# PCB-BI8-1x6SC3.net
KiCad netlist of a schematic drawn in EAGLE
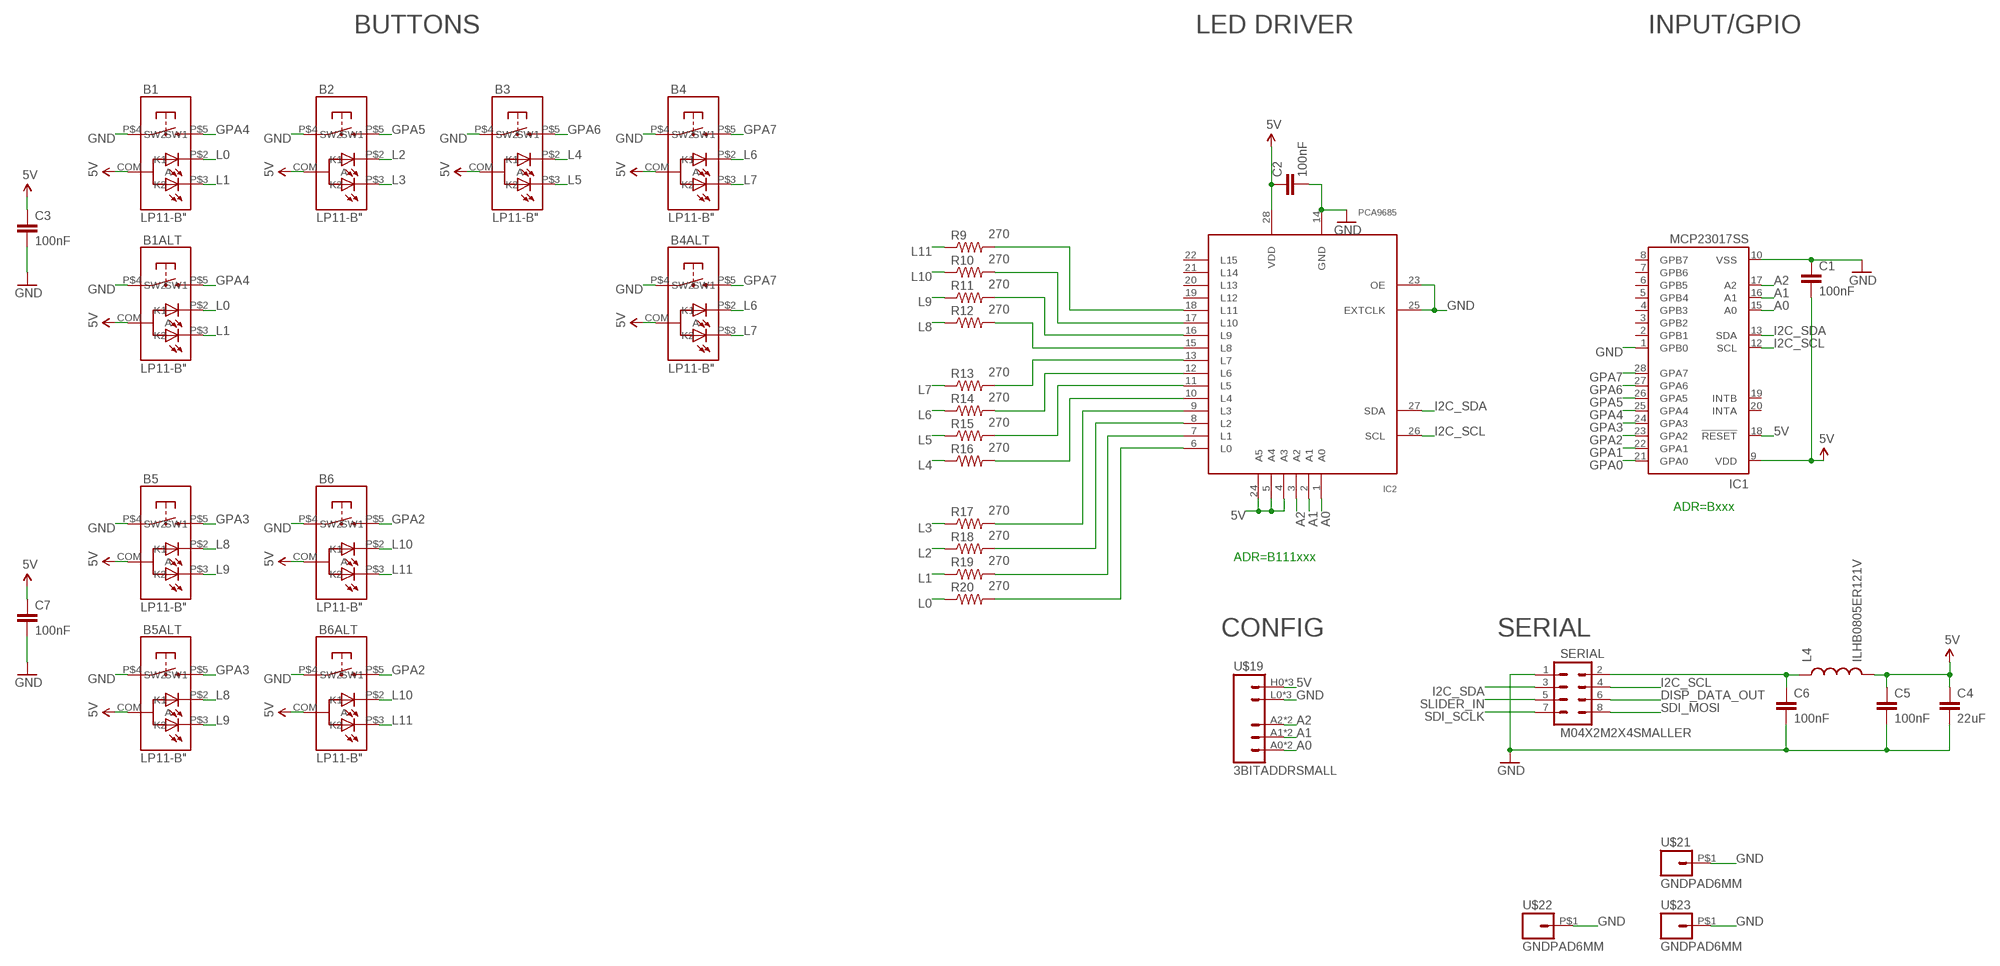
[diagram p0: schematic, sheet 1]

(export (version "E")
  (design (tool "Eeschema 10.0.6"))
  (components
    (comp (ref "B1")
      (value "LP11-B\"")
      (footprint "eagle-import:LP11")
      (libsource (lib "eagle-import") (part "LP11-B{dblquote}"))
    )
    (comp (ref "B1ALT")
      (value "LP11-B\"")
      (footprint "eagle-import:LP11")
      (libsource (lib "eagle-import") (part "LP11-B{dblquote}"))
    )
    (comp (ref "B2")
      (value "LP11-B\"")
      (footprint "eagle-import:LP11")
      (libsource (lib "eagle-import") (part "LP11-B{dblquote}"))
    )
    (comp (ref "B3")
      (value "LP11-B\"")
      (footprint "eagle-import:LP11")
      (libsource (lib "eagle-import") (part "LP11-B{dblquote}"))
    )
    (comp (ref "B4")
      (value "LP11-B\"")
      (footprint "eagle-import:LP11")
      (libsource (lib "eagle-import") (part "LP11-B{dblquote}"))
    )
    (comp (ref "B4ALT")
      (value "LP11-B\"")
      (footprint "eagle-import:LP11")
      (libsource (lib "eagle-import") (part "LP11-B{dblquote}"))
    )
    (comp (ref "B5")
      (value "LP11-B\"")
      (footprint "eagle-import:LP11")
      (libsource (lib "eagle-import") (part "LP11-B{dblquote}"))
    )
    (comp (ref "B5ALT")
      (value "LP11-B\"")
      (footprint "eagle-import:LP11")
      (libsource (lib "eagle-import") (part "LP11-B{dblquote}"))
    )
    (comp (ref "B6")
      (value "LP11-B\"")
      (footprint "eagle-import:LP11")
      (libsource (lib "eagle-import") (part "LP11-B{dblquote}"))
    )
    (comp (ref "B6ALT")
      (value "LP11-B\"")
      (footprint "eagle-import:LP11")
      (libsource (lib "eagle-import") (part "LP11-B{dblquote}"))
    )
    (comp (ref "C1")
      (value "100nF")
      (footprint "eagle-import:0603-CAP")
      (libsource (lib "eagle-import") (part "CAP0603-CAP"))
    )
    (comp (ref "C2")
      (value "100nF")
      (footprint "eagle-import:0603-CAP")
      (libsource (lib "eagle-import") (part "CAP0603-CAP"))
    )
    (comp (ref "C3")
      (value "100nF")
      (footprint "eagle-import:0603-CAP")
      (libsource (lib "eagle-import") (part "CAP0603-CAP"))
    )
    (comp (ref "C4")
      (value "22uF")
      (footprint "eagle-import:0805")
      (libsource (lib "eagle-import") (part "CAP0805"))
    )
    (comp (ref "C5")
      (value "100nF")
      (footprint "eagle-import:0603-CAP")
      (libsource (lib "eagle-import") (part "CAP0603-CAP"))
    )
    (comp (ref "C6")
      (value "100nF")
      (footprint "eagle-import:0603-CAP")
      (libsource (lib "eagle-import") (part "CAP0603-CAP"))
    )
    (comp (ref "C7")
      (value "100nF")
      (footprint "eagle-import:0603-CAP")
      (libsource (lib "eagle-import") (part "CAP0603-CAP"))
    )
    (comp (ref "IC1")
      (value "MCP23017SS")
      (footprint "eagle-import:SSOP28")
      (fields
        (field (name "MF") "MICROCHIP")
        (field (name "MPN") "MCP23017-E/SS")
        (field (name "MPN_1") "MCP23017-E/SS")
        (field (name "OC_FARNELL") "1467674")
        (field (name "OC_NEWARK") "31K2960")
      )
      (libsource (lib "eagle-import") (part "MCP23017SS"))
    )
    (comp (ref "IC2")
      (value "PCA9685")
      (footprint "eagle-import:TSSOP28")
      (libsource (lib "eagle-import") (part "PCA9685"))
    )
    (comp (ref "L4")
      (value "ILHB0805ER121V")
      (footprint "eagle-import:0805")
      (libsource (lib "eagle-import") (part "INDUCTOR0805"))
    )
    (comp (ref "R9")
      (value "270")
      (footprint "eagle-import:0603-RES")
      (libsource (lib "eagle-import") (part "RESISTOR0603-RES"))
    )
    (comp (ref "R10")
      (value "270")
      (footprint "eagle-import:0603-RES")
      (libsource (lib "eagle-import") (part "RESISTOR0603-RES"))
    )
    (comp (ref "R11")
      (value "270")
      (footprint "eagle-import:0603-RES")
      (libsource (lib "eagle-import") (part "RESISTOR0603-RES"))
    )
    (comp (ref "R12")
      (value "270")
      (footprint "eagle-import:0603-RES")
      (libsource (lib "eagle-import") (part "RESISTOR0603-RES"))
    )
    (comp (ref "R13")
      (value "270")
      (footprint "eagle-import:0603-RES")
      (libsource (lib "eagle-import") (part "RESISTOR0603-RES"))
    )
    (comp (ref "R14")
      (value "270")
      (footprint "eagle-import:0603-RES")
      (libsource (lib "eagle-import") (part "RESISTOR0603-RES"))
    )
    (comp (ref "R15")
      (value "270")
      (footprint "eagle-import:0603-RES")
      (libsource (lib "eagle-import") (part "RESISTOR0603-RES"))
    )
    (comp (ref "R16")
      (value "270")
      (footprint "eagle-import:0603-RES")
      (libsource (lib "eagle-import") (part "RESISTOR0603-RES"))
    )
    (comp (ref "R17")
      (value "270")
      (footprint "eagle-import:0603-RES")
      (libsource (lib "eagle-import") (part "RESISTOR0603-RES"))
    )
    (comp (ref "R18")
      (value "270")
      (footprint "eagle-import:0603-RES")
      (libsource (lib "eagle-import") (part "RESISTOR0603-RES"))
    )
    (comp (ref "R19")
      (value "270")
      (footprint "eagle-import:0603-RES")
      (libsource (lib "eagle-import") (part "RESISTOR0603-RES"))
    )
    (comp (ref "R20")
      (value "270")
      (footprint "eagle-import:0603-RES")
      (libsource (lib "eagle-import") (part "RESISTOR0603-RES"))
    )
    (comp (ref "SERIAL")
      (value "M04X2M2X4SMALLER")
      (footprint "eagle-import:M2X4SMALLER")
      (libsource (lib "eagle-import") (part "M04X2M2X4SMALLER"))
    )
    (comp (ref "U$19")
      (value "3BITADDRSMALL")
      (footprint "eagle-import:3BITADDR_SMALL")
      (libsource (lib "eagle-import") (part "3BITADDRSMALL"))
    )
    (comp (ref "U$21")
      (value "GNDPAD6MM")
      (footprint "eagle-import:3.2MMPAD6MM")
      (libsource (lib "eagle-import") (part "GNDPAD6MM"))
    )
    (comp (ref "U$22")
      (value "GNDPAD6MM")
      (footprint "eagle-import:3.2MMPAD6MM")
      (libsource (lib "eagle-import") (part "GNDPAD6MM"))
    )
    (comp (ref "U$23")
      (value "GNDPAD6MM")
      (footprint "eagle-import:3.2MMPAD6MM")
      (libsource (lib "eagle-import") (part "GNDPAD6MM"))
    )
  )
  (nets
    (net (code "1") (name "/A0") (class "Default")
      (node (ref "IC1") (pin "15") (pinfunction "A0_15") (pintype "input"))
      (node (ref "IC2") (pin "1") (pinfunction "A0_1") (pintype "input"))
      (node (ref "U$19") (pin "A0") (pinfunction "A0_A0") (pintype "passive"))
      (node (ref "U$19") (pin "AS0") (pinfunction "A0_AS0") (pintype "passive"))
    )
    (net (code "2") (name "/A1") (class "Default")
      (node (ref "IC1") (pin "16") (pinfunction "A1_16") (pintype "input"))
      (node (ref "IC2") (pin "2") (pinfunction "A1_2") (pintype "input"))
      (node (ref "U$19") (pin "A1") (pinfunction "A1_A1") (pintype "passive"))
      (node (ref "U$19") (pin "AS1") (pinfunction "A1_AS1") (pintype "passive"))
    )
    (net (code "3") (name "/A2") (class "Default")
      (node (ref "IC1") (pin "17") (pinfunction "A2_17") (pintype "input"))
      (node (ref "IC2") (pin "3") (pinfunction "A2_3") (pintype "input"))
      (node (ref "U$19") (pin "A2") (pinfunction "A2_A2") (pintype "passive"))
      (node (ref "U$19") (pin "AS2") (pinfunction "A2_AS2") (pintype "passive"))
    )
    (net (code "4") (name "/DISP_DATA_OUT") (class "Default")
      (node (ref "SERIAL") (pin "6") (pinfunction "6_6") (pintype "passive"))
    )
    (net (code "5") (name "/GPA0") (class "Default")
      (node (ref "IC1") (pin "21") (pinfunction "GPA0_21") (pintype "bidirectional"))
    )
    (net (code "6") (name "/GPA1") (class "Default")
      (node (ref "IC1") (pin "22") (pinfunction "GPA1_22") (pintype "bidirectional"))
    )
    (net (code "7") (name "/GPA2") (class "Default")
      (node (ref "B6") (pin "P$5") (pinfunction "SW2_P$5") (pintype "bidirectional"))
      (node (ref "B6ALT") (pin "P$5") (pinfunction "SW2_P$5") (pintype "bidirectional"))
      (node (ref "IC1") (pin "23") (pinfunction "GPA2_23") (pintype "bidirectional"))
    )
    (net (code "8") (name "/GPA3") (class "Default")
      (node (ref "B5") (pin "P$5") (pinfunction "SW2_P$5") (pintype "bidirectional"))
      (node (ref "B5ALT") (pin "P$5") (pinfunction "SW2_P$5") (pintype "bidirectional"))
      (node (ref "IC1") (pin "24") (pinfunction "GPA3_24") (pintype "bidirectional"))
    )
    (net (code "9") (name "/GPA4") (class "Default")
      (node (ref "B1") (pin "P$5") (pinfunction "SW2_P$5") (pintype "bidirectional"))
      (node (ref "B1ALT") (pin "P$5") (pinfunction "SW2_P$5") (pintype "bidirectional"))
      (node (ref "IC1") (pin "25") (pinfunction "GPA4_25") (pintype "bidirectional"))
    )
    (net (code "10") (name "/GPA5") (class "Default")
      (node (ref "B2") (pin "P$5") (pinfunction "SW2_P$5") (pintype "bidirectional"))
      (node (ref "IC1") (pin "26") (pinfunction "GPA5_26") (pintype "bidirectional"))
    )
    (net (code "11") (name "/GPA6") (class "Default")
      (node (ref "B3") (pin "P$5") (pinfunction "SW2_P$5") (pintype "bidirectional"))
      (node (ref "IC1") (pin "27") (pinfunction "GPA6_27") (pintype "bidirectional"))
    )
    (net (code "12") (name "/GPA7") (class "Default")
      (node (ref "B4") (pin "P$5") (pinfunction "SW2_P$5") (pintype "bidirectional"))
      (node (ref "B4ALT") (pin "P$5") (pinfunction "SW2_P$5") (pintype "bidirectional"))
      (node (ref "IC1") (pin "28") (pinfunction "GPA7_28") (pintype "bidirectional"))
    )
    (net (code "13") (name "/I2C_SCL") (class "Default")
      (node (ref "IC1") (pin "12") (pinfunction "SCL_12") (pintype "input"))
      (node (ref "IC2") (pin "26") (pinfunction "SCL_26") (pintype "input"))
      (node (ref "SERIAL") (pin "4") (pinfunction "4_4") (pintype "passive"))
    )
    (net (code "14") (name "/I2C_SDA") (class "Default")
      (node (ref "IC1") (pin "13") (pinfunction "SDA_13") (pintype "bidirectional"))
      (node (ref "IC2") (pin "27") (pinfunction "SDA_27") (pintype "input"))
      (node (ref "SERIAL") (pin "3") (pinfunction "3_3") (pintype "passive"))
    )
    (net (code "15") (name "/L0") (class "Default")
      (node (ref "B1") (pin "P$2") (pinfunction "K1_P$2") (pintype "bidirectional"))
      (node (ref "B1ALT") (pin "P$2") (pinfunction "K1_P$2") (pintype "bidirectional"))
      (node (ref "R20") (pin "1") (pinfunction "1_1") (pintype "passive"))
    )
    (net (code "16") (name "/L1") (class "Default")
      (node (ref "B1") (pin "P$3") (pinfunction "K2_P$3") (pintype "bidirectional"))
      (node (ref "B1ALT") (pin "P$3") (pinfunction "K2_P$3") (pintype "bidirectional"))
      (node (ref "R19") (pin "1") (pinfunction "1_1") (pintype "passive"))
    )
    (net (code "17") (name "/L2") (class "Default")
      (node (ref "B2") (pin "P$2") (pinfunction "K1_P$2") (pintype "bidirectional"))
      (node (ref "R18") (pin "1") (pinfunction "1_1") (pintype "passive"))
    )
    (net (code "18") (name "/L3") (class "Default")
      (node (ref "B2") (pin "P$3") (pinfunction "K2_P$3") (pintype "bidirectional"))
      (node (ref "R17") (pin "1") (pinfunction "1_1") (pintype "passive"))
    )
    (net (code "19") (name "/L4") (class "Default")
      (node (ref "B3") (pin "P$2") (pinfunction "K1_P$2") (pintype "bidirectional"))
      (node (ref "R16") (pin "1") (pinfunction "1_1") (pintype "passive"))
    )
    (net (code "20") (name "/L5") (class "Default")
      (node (ref "B3") (pin "P$3") (pinfunction "K2_P$3") (pintype "bidirectional"))
      (node (ref "R15") (pin "1") (pinfunction "1_1") (pintype "passive"))
    )
    (net (code "21") (name "/L6") (class "Default")
      (node (ref "B4") (pin "P$2") (pinfunction "K1_P$2") (pintype "bidirectional"))
      (node (ref "B4ALT") (pin "P$2") (pinfunction "K1_P$2") (pintype "bidirectional"))
      (node (ref "R14") (pin "1") (pinfunction "1_1") (pintype "passive"))
    )
    (net (code "22") (name "/L7") (class "Default")
      (node (ref "B4") (pin "P$3") (pinfunction "K2_P$3") (pintype "bidirectional"))
      (node (ref "B4ALT") (pin "P$3") (pinfunction "K2_P$3") (pintype "bidirectional"))
      (node (ref "R13") (pin "1") (pinfunction "1_1") (pintype "passive"))
    )
    (net (code "23") (name "/L8") (class "Default")
      (node (ref "B5") (pin "P$2") (pinfunction "K1_P$2") (pintype "bidirectional"))
      (node (ref "B5ALT") (pin "P$2") (pinfunction "K1_P$2") (pintype "bidirectional"))
      (node (ref "R12") (pin "1") (pinfunction "1_1") (pintype "passive"))
    )
    (net (code "24") (name "/L9") (class "Default")
      (node (ref "B5") (pin "P$3") (pinfunction "K2_P$3") (pintype "bidirectional"))
      (node (ref "B5ALT") (pin "P$3") (pinfunction "K2_P$3") (pintype "bidirectional"))
      (node (ref "R11") (pin "1") (pinfunction "1_1") (pintype "passive"))
    )
    (net (code "25") (name "/L10") (class "Default")
      (node (ref "B6") (pin "P$2") (pinfunction "K1_P$2") (pintype "bidirectional"))
      (node (ref "B6ALT") (pin "P$2") (pinfunction "K1_P$2") (pintype "bidirectional"))
      (node (ref "R10") (pin "1") (pinfunction "1_1") (pintype "passive"))
    )
    (net (code "26") (name "/L11") (class "Default")
      (node (ref "B6") (pin "P$3") (pinfunction "K2_P$3") (pintype "bidirectional"))
      (node (ref "B6ALT") (pin "P$3") (pinfunction "K2_P$3") (pintype "bidirectional"))
      (node (ref "R9") (pin "1") (pinfunction "1_1") (pintype "passive"))
    )
    (net (code "27") (name "/SDI_MOSI") (class "Default")
      (node (ref "SERIAL") (pin "8") (pinfunction "8_8") (pintype "passive"))
    )
    (net (code "28") (name "/SDI_SCLK") (class "Default")
      (node (ref "SERIAL") (pin "7") (pinfunction "7_7") (pintype "passive"))
    )
    (net (code "29") (name "/SLIDER_IN") (class "Default")
      (node (ref "SERIAL") (pin "5") (pinfunction "5_5") (pintype "passive"))
    )
    (net (code "30") (name "5V") (class "Default")
      (node (ref "B1") (pin "COM") (pinfunction "A_COM") (pintype "bidirectional"))
      (node (ref "B1ALT") (pin "COM") (pinfunction "A_COM") (pintype "bidirectional"))
      (node (ref "B2") (pin "COM") (pinfunction "A_COM") (pintype "bidirectional"))
      (node (ref "B3") (pin "COM") (pinfunction "A_COM") (pintype "bidirectional"))
      (node (ref "B4") (pin "COM") (pinfunction "A_COM") (pintype "bidirectional"))
      (node (ref "B4ALT") (pin "COM") (pinfunction "A_COM") (pintype "bidirectional"))
      (node (ref "B5") (pin "COM") (pinfunction "A_COM") (pintype "bidirectional"))
      (node (ref "B5ALT") (pin "COM") (pinfunction "A_COM") (pintype "bidirectional"))
      (node (ref "B6") (pin "COM") (pinfunction "A_COM") (pintype "bidirectional"))
      (node (ref "B6ALT") (pin "COM") (pinfunction "A_COM") (pintype "bidirectional"))
      (node (ref "C1") (pin "2") (pinfunction "2_2") (pintype "passive"))
      (node (ref "C2") (pin "1") (pinfunction "1_1") (pintype "passive"))
      (node (ref "C3") (pin "1") (pinfunction "1_1") (pintype "passive"))
      (node (ref "C4") (pin "1") (pinfunction "1_1") (pintype "passive"))
      (node (ref "C5") (pin "1") (pinfunction "1_1") (pintype "passive"))
      (node (ref "C7") (pin "1") (pinfunction "1_1") (pintype "passive"))
      (node (ref "IC1") (pin "18") (pinfunction "~{RESET}_18") (pintype "input"))
      (node (ref "IC1") (pin "9") (pinfunction "VDD_9") (pintype "power_in"))
      (node (ref "IC2") (pin "24") (pinfunction "A5_24") (pintype "input"))
      (node (ref "IC2") (pin "28") (pinfunction "VDD_28") (pintype "power_in"))
      (node (ref "IC2") (pin "4") (pinfunction "A3_4") (pintype "input"))
      (node (ref "IC2") (pin "5") (pinfunction "A4_5") (pintype "input"))
      (node (ref "L4") (pin "2") (pinfunction "2_2") (pintype "passive"))
      (node (ref "U$19") (pin "H0") (pinfunction "VCC_H0") (pintype "passive"))
      (node (ref "U$19") (pin "H1") (pinfunction "VCC_H1") (pintype "passive"))
      (node (ref "U$19") (pin "H2") (pinfunction "VCC_H2") (pintype "passive"))
    )
    (net (code "31") (name "GND") (class "Default")
      (node (ref "B1") (pin "P$4") (pinfunction "SW1_P$4") (pintype "bidirectional"))
      (node (ref "B1ALT") (pin "P$4") (pinfunction "SW1_P$4") (pintype "bidirectional"))
      (node (ref "B2") (pin "P$4") (pinfunction "SW1_P$4") (pintype "bidirectional"))
      (node (ref "B3") (pin "P$4") (pinfunction "SW1_P$4") (pintype "bidirectional"))
      (node (ref "B4") (pin "P$4") (pinfunction "SW1_P$4") (pintype "bidirectional"))
      (node (ref "B4ALT") (pin "P$4") (pinfunction "SW1_P$4") (pintype "bidirectional"))
      (node (ref "B5") (pin "P$4") (pinfunction "SW1_P$4") (pintype "bidirectional"))
      (node (ref "B5ALT") (pin "P$4") (pinfunction "SW1_P$4") (pintype "bidirectional"))
      (node (ref "B6") (pin "P$4") (pinfunction "SW1_P$4") (pintype "bidirectional"))
      (node (ref "B6ALT") (pin "P$4") (pinfunction "SW1_P$4") (pintype "bidirectional"))
      (node (ref "C1") (pin "1") (pinfunction "1_1") (pintype "passive"))
      (node (ref "C2") (pin "2") (pinfunction "2_2") (pintype "passive"))
      (node (ref "C3") (pin "2") (pinfunction "2_2") (pintype "passive"))
      (node (ref "C4") (pin "2") (pinfunction "2_2") (pintype "passive"))
      (node (ref "C5") (pin "2") (pinfunction "2_2") (pintype "passive"))
      (node (ref "C6") (pin "2") (pinfunction "2_2") (pintype "passive"))
      (node (ref "C7") (pin "2") (pinfunction "2_2") (pintype "passive"))
      (node (ref "IC1") (pin "1") (pinfunction "GPB0_1") (pintype "bidirectional"))
      (node (ref "IC1") (pin "10") (pinfunction "VSS_10") (pintype "power_in"))
      (node (ref "IC2") (pin "14") (pinfunction "GND_14") (pintype "power_in"))
      (node (ref "IC2") (pin "23") (pinfunction "OE_23") (pintype "input"))
      (node (ref "IC2") (pin "25") (pinfunction "EXTCLK_25") (pintype "input"))
      (node (ref "SERIAL") (pin "1") (pinfunction "1_1") (pintype "passive"))
      (node (ref "U$19") (pin "L0") (pinfunction "GND_L0") (pintype "passive"))
      (node (ref "U$19") (pin "L1") (pinfunction "GND_L1") (pintype "passive"))
      (node (ref "U$19") (pin "L2") (pinfunction "GND_L2") (pintype "passive"))
      (node (ref "U$21") (pin "P$1") (pinfunction "1_P$1") (pintype "passive"))
      (node (ref "U$22") (pin "P$1") (pinfunction "1_P$1") (pintype "passive"))
      (node (ref "U$23") (pin "P$1") (pinfunction "1_P$1") (pintype "passive"))
    )
    (net (code "32") (name "Net-(C6-Pad1)") (class "Default")
      (node (ref "C6") (pin "1") (pinfunction "1_1") (pintype "passive"))
      (node (ref "L4") (pin "1") (pinfunction "1_1") (pintype "passive"))
      (node (ref "SERIAL") (pin "2") (pinfunction "2_2") (pintype "passive"))
    )
    (net (code "33") (name "Net-(IC2-L0)") (class "Default")
      (node (ref "IC2") (pin "6") (pinfunction "L0_6") (pintype "output"))
      (node (ref "R20") (pin "2") (pinfunction "2_2") (pintype "passive"))
    )
    (net (code "34") (name "Net-(IC2-L1)") (class "Default")
      (node (ref "IC2") (pin "7") (pinfunction "L1_7") (pintype "output"))
      (node (ref "R19") (pin "2") (pinfunction "2_2") (pintype "passive"))
    )
    (net (code "35") (name "Net-(IC2-L2)") (class "Default")
      (node (ref "IC2") (pin "8") (pinfunction "L2_8") (pintype "output"))
      (node (ref "R18") (pin "2") (pinfunction "2_2") (pintype "passive"))
    )
    (net (code "36") (name "Net-(IC2-L3)") (class "Default")
      (node (ref "IC2") (pin "9") (pinfunction "L3_9") (pintype "output"))
      (node (ref "R17") (pin "2") (pinfunction "2_2") (pintype "passive"))
    )
    (net (code "37") (name "Net-(IC2-L4)") (class "Default")
      (node (ref "IC2") (pin "10") (pinfunction "L4_10") (pintype "output"))
      (node (ref "R16") (pin "2") (pinfunction "2_2") (pintype "passive"))
    )
    (net (code "38") (name "Net-(IC2-L5)") (class "Default")
      (node (ref "IC2") (pin "11") (pinfunction "L5_11") (pintype "output"))
      (node (ref "R15") (pin "2") (pinfunction "2_2") (pintype "passive"))
    )
    (net (code "39") (name "Net-(IC2-L6)") (class "Default")
      (node (ref "IC2") (pin "12") (pinfunction "L6_12") (pintype "output"))
      (node (ref "R14") (pin "2") (pinfunction "2_2") (pintype "passive"))
    )
    (net (code "40") (name "Net-(IC2-L7)") (class "Default")
      (node (ref "IC2") (pin "13") (pinfunction "L7_13") (pintype "output"))
      (node (ref "R13") (pin "2") (pinfunction "2_2") (pintype "passive"))
    )
    (net (code "41") (name "Net-(IC2-L8)") (class "Default")
      (node (ref "IC2") (pin "15") (pinfunction "L8_15") (pintype "output"))
      (node (ref "R12") (pin "2") (pinfunction "2_2") (pintype "passive"))
    )
    (net (code "42") (name "Net-(IC2-L9)") (class "Default")
      (node (ref "IC2") (pin "16") (pinfunction "L9_16") (pintype "output"))
      (node (ref "R11") (pin "2") (pinfunction "2_2") (pintype "passive"))
    )
    (net (code "43") (name "Net-(IC2-L10)") (class "Default")
      (node (ref "IC2") (pin "17") (pinfunction "L10_17") (pintype "output"))
      (node (ref "R10") (pin "2") (pinfunction "2_2") (pintype "passive"))
    )
    (net (code "44") (name "Net-(IC2-L11)") (class "Default")
      (node (ref "IC2") (pin "18") (pinfunction "L11_18") (pintype "output"))
      (node (ref "R9") (pin "2") (pinfunction "2_2") (pintype "passive"))
    )
    (net (code "45") (name "unconnected-(IC1-GPB1-Pad2)") (class "Default")
      (node (ref "IC1") (pin "2") (pinfunction "GPB1_2") (pintype "bidirectional"))
    )
    (net (code "46") (name "unconnected-(IC1-GPB2-Pad3)") (class "Default")
      (node (ref "IC1") (pin "3") (pinfunction "GPB2_3") (pintype "bidirectional"))
    )
    (net (code "47") (name "unconnected-(IC1-GPB3-Pad4)") (class "Default")
      (node (ref "IC1") (pin "4") (pinfunction "GPB3_4") (pintype "bidirectional"))
    )
    (net (code "48") (name "unconnected-(IC1-GPB4-Pad5)") (class "Default")
      (node (ref "IC1") (pin "5") (pinfunction "GPB4_5") (pintype "bidirectional"))
    )
    (net (code "49") (name "unconnected-(IC1-GPB5-Pad6)") (class "Default")
      (node (ref "IC1") (pin "6") (pinfunction "GPB5_6") (pintype "bidirectional"))
    )
    (net (code "50") (name "unconnected-(IC1-GPB6-Pad7)") (class "Default")
      (node (ref "IC1") (pin "7") (pinfunction "GPB6_7") (pintype "bidirectional"))
    )
    (net (code "51") (name "unconnected-(IC1-GPB7-Pad8)") (class "Default")
      (node (ref "IC1") (pin "8") (pinfunction "GPB7_8") (pintype "bidirectional"))
    )
    (net (code "52") (name "unconnected-(IC1-INTA-Pad20)") (class "Default")
      (node (ref "IC1") (pin "20") (pinfunction "INTA_20") (pintype "output"))
    )
    (net (code "53") (name "unconnected-(IC1-INTB-Pad19)") (class "Default")
      (node (ref "IC1") (pin "19") (pinfunction "INTB_19") (pintype "output"))
    )
    (net (code "54") (name "unconnected-(IC2-L12-Pad19)") (class "Default")
      (node (ref "IC2") (pin "19") (pinfunction "L12_19") (pintype "output"))
    )
    (net (code "55") (name "unconnected-(IC2-L13-Pad20)") (class "Default")
      (node (ref "IC2") (pin "20") (pinfunction "L13_20") (pintype "output"))
    )
    (net (code "56") (name "unconnected-(IC2-L14-Pad21)") (class "Default")
      (node (ref "IC2") (pin "21") (pinfunction "L14_21") (pintype "output"))
    )
    (net (code "57") (name "unconnected-(IC2-L15-Pad22)") (class "Default")
      (node (ref "IC2") (pin "22") (pinfunction "L15_22") (pintype "output"))
    )
  )
)
